# indicator_pcb.net
KiCad netlist of a schematic drawn in EAGLE
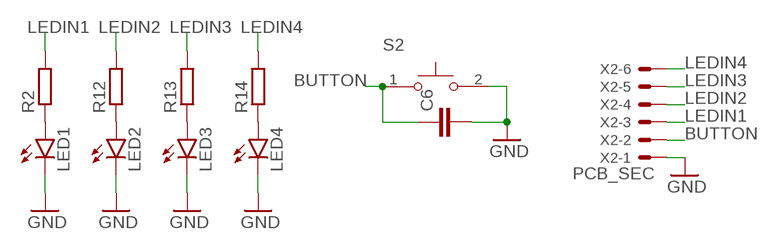
[diagram p0: schematic, sheet 1]

(export (version "E")
  (design (tool "Eeschema 10.0.6"))
  (components
    (comp (ref "C6")
      (value "C-EUC0603")
      (footprint "eagle-import:C0603")
      (libsource (lib "eagle-import") (part "C-EUC0603"))
    )
    (comp (ref "LED1")
      (value "LEDCHIP-LED0805")
      (footprint "eagle-import:CHIP-LED0805")
      (libsource (lib "eagle-import") (part "LEDCHIP-LED0805"))
    )
    (comp (ref "LED2")
      (value "LEDCHIP-LED0805")
      (footprint "eagle-import:CHIP-LED0805")
      (libsource (lib "eagle-import") (part "LEDCHIP-LED0805"))
    )
    (comp (ref "LED3")
      (value "LEDCHIP-LED0805")
      (footprint "eagle-import:CHIP-LED0805")
      (libsource (lib "eagle-import") (part "LEDCHIP-LED0805"))
    )
    (comp (ref "LED4")
      (value "LEDCHIP-LED0805")
      (footprint "eagle-import:CHIP-LED0805")
      (libsource (lib "eagle-import") (part "LEDCHIP-LED0805"))
    )
    (comp (ref "R2")
      (value "R-EU_R0805")
      (footprint "eagle-import:R0805")
      (libsource (lib "eagle-import") (part "R-EU_R0805"))
    )
    (comp (ref "R12")
      (value "R-EU_R0805")
      (footprint "eagle-import:R0805")
      (libsource (lib "eagle-import") (part "R-EU_R0805"))
    )
    (comp (ref "R13")
      (value "R-EU_R0805")
      (footprint "eagle-import:R0805")
      (libsource (lib "eagle-import") (part "R-EU_R0805"))
    )
    (comp (ref "R14")
      (value "R-EU_R0805")
      (footprint "eagle-import:R0805")
      (libsource (lib "eagle-import") (part "R-EU_R0805"))
    )
    (comp (ref "S2")
      (value "TL9210AF180Q")
      (footprint "eagle-import:SW_TL9210AF180Q")
      (fields (field (name "MF") "E-Switch"))
      (libsource (lib "eagle-import") (part "TL9210AF180Q"))
    )
    (comp (ref "X2")
      (value "PCB_SEC")
      (footprint "eagle-import:JST-XH-06-PACKAGE-LONG-PAD")
      (libsource (lib "eagle-import") (part "JST-XH-06-PIN-LONG-PAD"))
    )
  )
  (nets
    (net (code "1") (name "/BUTTON") (class "Default")
      (node (ref "C6") (pin "1") (pinfunction "1_1") (pintype "passive"))
      (node (ref "S2") (pin "1") (pinfunction "1_1") (pintype "passive"))
      (node (ref "X2") (pin "2") (pinfunction "S_2") (pintype "passive"))
    )
    (net (code "2") (name "/LEDIN1") (class "Default")
      (node (ref "R2") (pin "2") (pinfunction "2_2") (pintype "passive"))
      (node (ref "X2") (pin "3") (pinfunction "S_3") (pintype "passive"))
    )
    (net (code "3") (name "/LEDIN2") (class "Default")
      (node (ref "R12") (pin "2") (pinfunction "2_2") (pintype "passive"))
      (node (ref "X2") (pin "4") (pinfunction "S_4") (pintype "passive"))
    )
    (net (code "4") (name "/LEDIN3") (class "Default")
      (node (ref "R13") (pin "2") (pinfunction "2_2") (pintype "passive"))
      (node (ref "X2") (pin "5") (pinfunction "S_5") (pintype "passive"))
    )
    (net (code "5") (name "/LEDIN4") (class "Default")
      (node (ref "R14") (pin "2") (pinfunction "2_2") (pintype "passive"))
      (node (ref "X2") (pin "6") (pinfunction "S_6") (pintype "passive"))
    )
    (net (code "6") (name "GND") (class "Default")
      (node (ref "C6") (pin "2") (pinfunction "2_2") (pintype "passive"))
      (node (ref "LED1") (pin "C") (pinfunction "C_C") (pintype "passive"))
      (node (ref "LED2") (pin "C") (pinfunction "C_C") (pintype "passive"))
      (node (ref "LED3") (pin "C") (pinfunction "C_C") (pintype "passive"))
      (node (ref "LED4") (pin "C") (pinfunction "C_C") (pintype "passive"))
      (node (ref "S2") (pin "2") (pinfunction "2_2") (pintype "passive"))
      (node (ref "X2") (pin "1") (pinfunction "S_1") (pintype "passive"))
    )
    (net (code "7") (name "Net-(LED1-PadA)") (class "Default")
      (node (ref "LED1") (pin "A") (pinfunction "A_A") (pintype "passive"))
      (node (ref "R2") (pin "1") (pinfunction "1_1") (pintype "passive"))
    )
    (net (code "8") (name "Net-(LED2-PadA)") (class "Default")
      (node (ref "LED2") (pin "A") (pinfunction "A_A") (pintype "passive"))
      (node (ref "R12") (pin "1") (pinfunction "1_1") (pintype "passive"))
    )
    (net (code "9") (name "Net-(LED3-PadA)") (class "Default")
      (node (ref "LED3") (pin "A") (pinfunction "A_A") (pintype "passive"))
      (node (ref "R13") (pin "1") (pinfunction "1_1") (pintype "passive"))
    )
    (net (code "10") (name "Net-(LED4-PadA)") (class "Default")
      (node (ref "LED4") (pin "A") (pinfunction "A_A") (pintype "passive"))
      (node (ref "R14") (pin "1") (pinfunction "1_1") (pintype "passive"))
    )
  )
)
